# Sheet1.net
KiCad netlist of a schematic drawn in Altium Designer
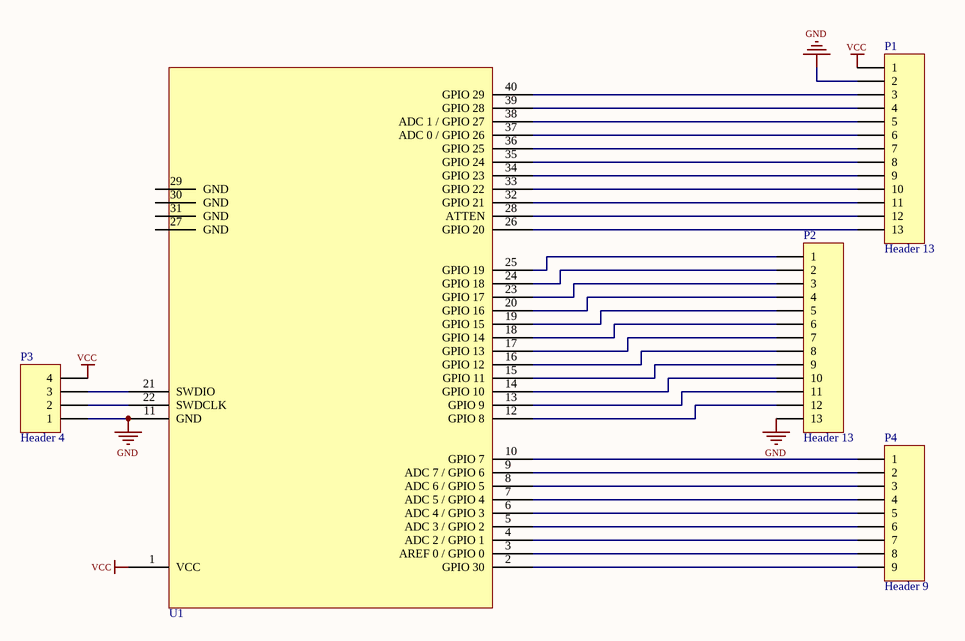
[diagram p0: Sheet1.SchDoc]

(export (version "E")
  (design (tool "Eeschema 10.0.6"))
  (components
    (comp (ref "P1")
      (value "Header 13")
      (footprint "HDR1X13")
      (description "Header, 13-Pin")
      (fields (field (name "PUBLISHER") "Altium Limited"))
      (libsource (lib "Miscellaneous Connectors") (part "Header 13"))
    )
    (comp (ref "P2")
      (value "Header 13")
      (footprint "HDR1X13")
      (description "Header, 13-Pin")
      (fields (field (name "PUBLISHER") "Altium Limited"))
      (libsource (lib "Miscellaneous Connectors") (part "Header 13"))
    )
    (comp (ref "P3")
      (value "Header 4")
      (footprint "HDR1X4")
      (description "Header, 4-Pin")
      (fields (field (name "PUBLISHER") "Altium Limited"))
      (libsource (lib "Miscellaneous Connectors") (part "Header 4"))
    )
    (comp (ref "P4")
      (value "Header 9")
      (footprint "HDR1X9")
      (description "Header, 9-Pin")
      (fields (field (name "PUBLISHER") "Altium Limited"))
      (libsource (lib "Miscellaneous Connectors") (part "Header 9"))
    )
    (comp (ref "U1")
      (value "nRF51-01/02")
      (footprint "nRF51-01/02")
      (description "Bluetooth uController")
      (libsource (lib "drewsparts") (part "nRF51-01/02"))
    )
  )
  (nets
    (net (code "1") (name "GND") (class "Default")
      (node (ref "P1") (pin "2") (pinfunction "2_2") (pintype "passive"))
      (node (ref "P2") (pin "13") (pinfunction "13_13") (pintype "passive"))
      (node (ref "P3") (pin "1") (pinfunction "1_1") (pintype "passive"))
      (node (ref "U1") (pin "11") (pinfunction "GND_11") (pintype "passive"))
    )
    (net (code "2") (name "Net-(U1-ADC_0_{slash}_GPIO_26)") (class "Default")
      (node (ref "P1") (pin "6") (pinfunction "6_6") (pintype "passive"))
      (node (ref "U1") (pin "37") (pinfunction "ADC_0_/_GPIO_26_37") (pintype "passive"))
    )
    (net (code "3") (name "Net-(U1-ADC_1_{slash}_GPIO_27)") (class "Default")
      (node (ref "P1") (pin "5") (pinfunction "5_5") (pintype "passive"))
      (node (ref "U1") (pin "38") (pinfunction "ADC_1_/_GPIO_27_38") (pintype "passive"))
    )
    (net (code "4") (name "Net-(U1-ADC_2_{slash}_GPIO_1)") (class "Default")
      (node (ref "P4") (pin "7") (pinfunction "7_7") (pintype "passive"))
      (node (ref "U1") (pin "4") (pinfunction "ADC_2_/_GPIO_1_4") (pintype "passive"))
    )
    (net (code "5") (name "Net-(U1-ADC_3_{slash}_GPIO_2)") (class "Default")
      (node (ref "P4") (pin "6") (pinfunction "6_6") (pintype "passive"))
      (node (ref "U1") (pin "5") (pinfunction "ADC_3_/_GPIO_2_5") (pintype "passive"))
    )
    (net (code "6") (name "Net-(U1-ADC_4_{slash}_GPIO_3)") (class "Default")
      (node (ref "P4") (pin "5") (pinfunction "5_5") (pintype "passive"))
      (node (ref "U1") (pin "6") (pinfunction "ADC_4_/_GPIO_3_6") (pintype "passive"))
    )
    (net (code "7") (name "Net-(U1-ADC_5_{slash}_GPIO_4)") (class "Default")
      (node (ref "P4") (pin "4") (pinfunction "4_4") (pintype "passive"))
      (node (ref "U1") (pin "7") (pinfunction "ADC_5_/_GPIO_4_7") (pintype "passive"))
    )
    (net (code "8") (name "Net-(U1-ADC_6_{slash}_GPIO_5)") (class "Default")
      (node (ref "P4") (pin "3") (pinfunction "3_3") (pintype "passive"))
      (node (ref "U1") (pin "8") (pinfunction "ADC_6_/_GPIO_5_8") (pintype "passive"))
    )
    (net (code "9") (name "Net-(U1-ADC_7_{slash}_GPIO_6)") (class "Default")
      (node (ref "P4") (pin "2") (pinfunction "2_2") (pintype "passive"))
      (node (ref "U1") (pin "9") (pinfunction "ADC_7_/_GPIO_6_9") (pintype "passive"))
    )
    (net (code "10") (name "Net-(U1-AREF_0_{slash}_GPIO_0)") (class "Default")
      (node (ref "P4") (pin "8") (pinfunction "8_8") (pintype "passive"))
      (node (ref "U1") (pin "3") (pinfunction "AREF_0_/_GPIO_0_3") (pintype "passive"))
    )
    (net (code "11") (name "Net-(U1-ATTEN)") (class "Default")
      (node (ref "P1") (pin "12") (pinfunction "12_12") (pintype "passive"))
      (node (ref "U1") (pin "28") (pinfunction "ATTEN_28") (pintype "passive"))
    )
    (net (code "12") (name "Net-(U1-GPIO_7)") (class "Default")
      (node (ref "P4") (pin "1") (pinfunction "1_1") (pintype "passive"))
      (node (ref "U1") (pin "10") (pinfunction "GPIO_7_10") (pintype "passive"))
    )
    (net (code "13") (name "Net-(U1-GPIO_8)") (class "Default")
      (node (ref "P2") (pin "12") (pinfunction "12_12") (pintype "passive"))
      (node (ref "U1") (pin "12") (pinfunction "GPIO_8_12") (pintype "passive"))
    )
    (net (code "14") (name "Net-(U1-GPIO_9)") (class "Default")
      (node (ref "P2") (pin "11") (pinfunction "11_11") (pintype "passive"))
      (node (ref "U1") (pin "13") (pinfunction "GPIO_9_13") (pintype "passive"))
    )
    (net (code "15") (name "Net-(U1-GPIO_10)") (class "Default")
      (node (ref "P2") (pin "10") (pinfunction "10_10") (pintype "passive"))
      (node (ref "U1") (pin "14") (pinfunction "GPIO_10_14") (pintype "passive"))
    )
    (net (code "16") (name "Net-(U1-GPIO_11)") (class "Default")
      (node (ref "P2") (pin "9") (pinfunction "9_9") (pintype "passive"))
      (node (ref "U1") (pin "15") (pinfunction "GPIO_11_15") (pintype "passive"))
    )
    (net (code "17") (name "Net-(U1-GPIO_12)") (class "Default")
      (node (ref "P2") (pin "8") (pinfunction "8_8") (pintype "passive"))
      (node (ref "U1") (pin "16") (pinfunction "GPIO_12_16") (pintype "passive"))
    )
    (net (code "18") (name "Net-(U1-GPIO_13)") (class "Default")
      (node (ref "P2") (pin "7") (pinfunction "7_7") (pintype "passive"))
      (node (ref "U1") (pin "17") (pinfunction "GPIO_13_17") (pintype "passive"))
    )
    (net (code "19") (name "Net-(U1-GPIO_14)") (class "Default")
      (node (ref "P2") (pin "6") (pinfunction "6_6") (pintype "passive"))
      (node (ref "U1") (pin "18") (pinfunction "GPIO_14_18") (pintype "passive"))
    )
    (net (code "20") (name "Net-(U1-GPIO_15)") (class "Default")
      (node (ref "P2") (pin "5") (pinfunction "5_5") (pintype "passive"))
      (node (ref "U1") (pin "19") (pinfunction "GPIO_15_19") (pintype "passive"))
    )
    (net (code "21") (name "Net-(U1-GPIO_16)") (class "Default")
      (node (ref "P2") (pin "4") (pinfunction "4_4") (pintype "passive"))
      (node (ref "U1") (pin "20") (pinfunction "GPIO_16_20") (pintype "passive"))
    )
    (net (code "22") (name "Net-(U1-GPIO_17)") (class "Default")
      (node (ref "P2") (pin "3") (pinfunction "3_3") (pintype "passive"))
      (node (ref "U1") (pin "23") (pinfunction "GPIO_17_23") (pintype "passive"))
    )
    (net (code "23") (name "Net-(U1-GPIO_18)") (class "Default")
      (node (ref "P2") (pin "2") (pinfunction "2_2") (pintype "passive"))
      (node (ref "U1") (pin "24") (pinfunction "GPIO_18_24") (pintype "passive"))
    )
    (net (code "24") (name "Net-(U1-GPIO_19)") (class "Default")
      (node (ref "P2") (pin "1") (pinfunction "1_1") (pintype "passive"))
      (node (ref "U1") (pin "25") (pinfunction "GPIO_19_25") (pintype "passive"))
    )
    (net (code "25") (name "Net-(U1-GPIO_20)") (class "Default")
      (node (ref "P1") (pin "13") (pinfunction "13_13") (pintype "passive"))
      (node (ref "U1") (pin "26") (pinfunction "GPIO_20_26") (pintype "passive"))
    )
    (net (code "26") (name "Net-(U1-GPIO_21)") (class "Default")
      (node (ref "P1") (pin "11") (pinfunction "11_11") (pintype "passive"))
      (node (ref "U1") (pin "32") (pinfunction "GPIO_21_32") (pintype "passive"))
    )
    (net (code "27") (name "Net-(U1-GPIO_22)") (class "Default")
      (node (ref "P1") (pin "10") (pinfunction "10_10") (pintype "passive"))
      (node (ref "U1") (pin "33") (pinfunction "GPIO_22_33") (pintype "passive"))
    )
    (net (code "28") (name "Net-(U1-GPIO_23)") (class "Default")
      (node (ref "P1") (pin "9") (pinfunction "9_9") (pintype "passive"))
      (node (ref "U1") (pin "34") (pinfunction "GPIO_23_34") (pintype "passive"))
    )
    (net (code "29") (name "Net-(U1-GPIO_24)") (class "Default")
      (node (ref "P1") (pin "8") (pinfunction "8_8") (pintype "passive"))
      (node (ref "U1") (pin "35") (pinfunction "GPIO_24_35") (pintype "passive"))
    )
    (net (code "30") (name "Net-(U1-GPIO_25)") (class "Default")
      (node (ref "P1") (pin "7") (pinfunction "7_7") (pintype "passive"))
      (node (ref "U1") (pin "36") (pinfunction "GPIO_25_36") (pintype "passive"))
    )
    (net (code "31") (name "Net-(U1-GPIO_28)") (class "Default")
      (node (ref "P1") (pin "4") (pinfunction "4_4") (pintype "passive"))
      (node (ref "U1") (pin "39") (pinfunction "GPIO_28_39") (pintype "passive"))
    )
    (net (code "32") (name "Net-(U1-GPIO_29)") (class "Default")
      (node (ref "P1") (pin "3") (pinfunction "3_3") (pintype "passive"))
      (node (ref "U1") (pin "40") (pinfunction "GPIO_29_40") (pintype "passive"))
    )
    (net (code "33") (name "Net-(U1-GPIO_30)") (class "Default")
      (node (ref "P4") (pin "9") (pinfunction "9_9") (pintype "passive"))
      (node (ref "U1") (pin "2") (pinfunction "GPIO_30_2") (pintype "passive"))
    )
    (net (code "34") (name "Net-(U1-SWDCLK)") (class "Default")
      (node (ref "P3") (pin "2") (pinfunction "2_2") (pintype "passive"))
      (node (ref "U1") (pin "22") (pinfunction "SWDCLK_22") (pintype "passive"))
    )
    (net (code "35") (name "Net-(U1-SWDIO)") (class "Default")
      (node (ref "P3") (pin "3") (pinfunction "3_3") (pintype "passive"))
      (node (ref "U1") (pin "21") (pinfunction "SWDIO_21") (pintype "passive"))
    )
    (net (code "36") (name "VCC") (class "Default")
      (node (ref "P1") (pin "1") (pinfunction "1_1") (pintype "passive"))
      (node (ref "P3") (pin "4") (pinfunction "4_4") (pintype "passive"))
      (node (ref "U1") (pin "1") (pinfunction "VCC_1") (pintype "passive"))
    )
    (net (code "37") (name "unconnected-(U1-GND-Pad27)") (class "Default")
      (node (ref "U1") (pin "27") (pinfunction "GND_27") (pintype "passive"))
    )
    (net (code "38") (name "unconnected-(U1-GND-Pad29)") (class "Default")
      (node (ref "U1") (pin "29") (pinfunction "GND_29") (pintype "passive"))
    )
    (net (code "39") (name "unconnected-(U1-GND-Pad30)") (class "Default")
      (node (ref "U1") (pin "30") (pinfunction "GND_30") (pintype "passive"))
    )
    (net (code "40") (name "unconnected-(U1-GND-Pad31)") (class "Default")
      (node (ref "U1") (pin "31") (pinfunction "GND_31") (pintype "passive"))
    )
  )
)
